# Decoder.net
KiCad netlist of a schematic drawn in EAGLE
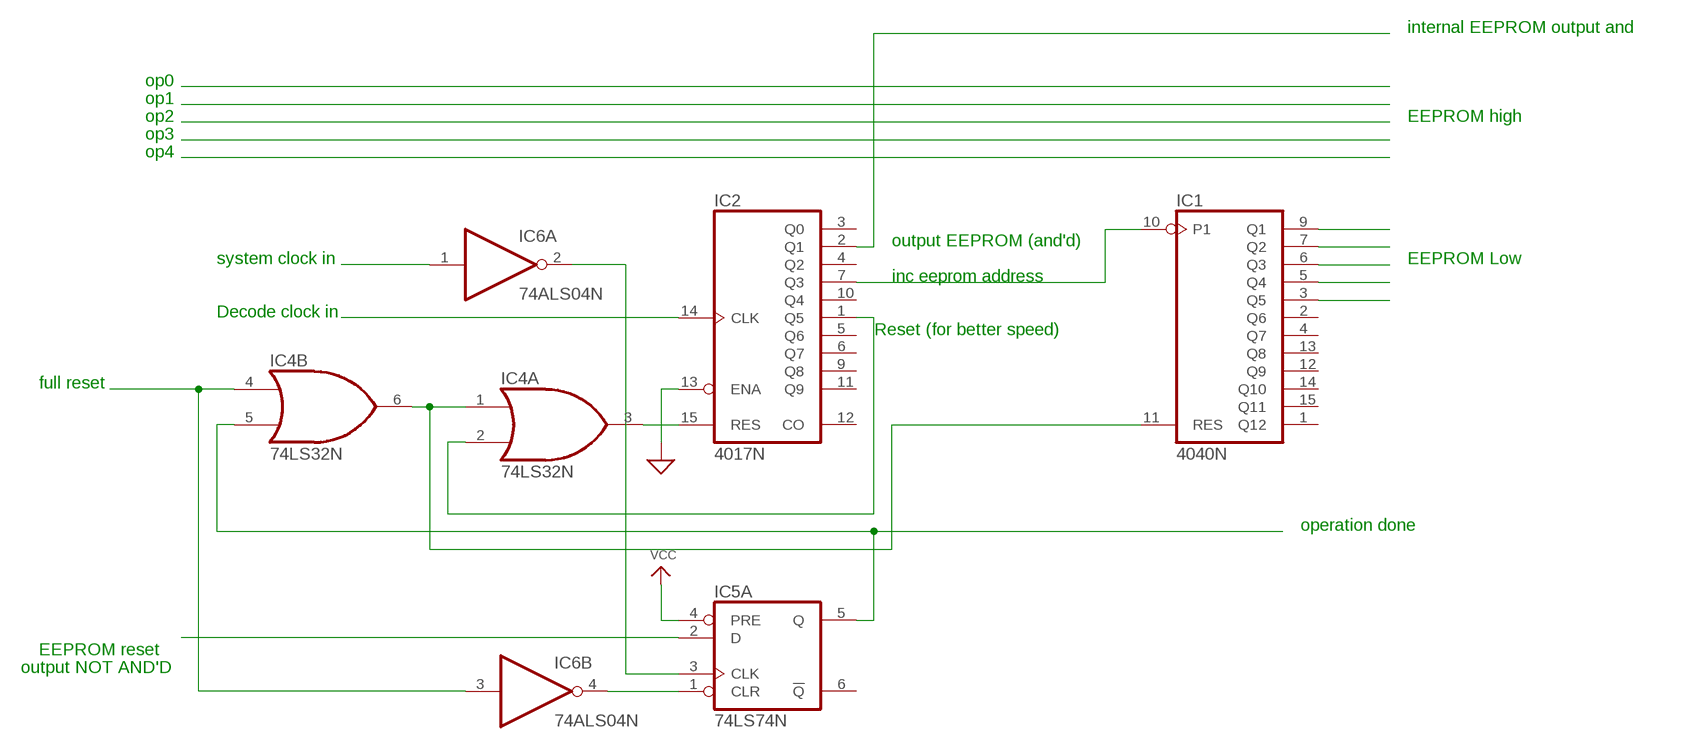
[diagram p0: schematic, sheet 1]

(export (version "E")
  (design (tool "Eeschema 10.0.6"))
  (components
    (comp (ref "IC1")
      (value "4040N")
      (footprint "eagle-import:DIL16")
      (libsource (lib "eagle-import") (part "4040N"))
    )
    (comp (ref "IC2")
      (value "4017N")
      (footprint "eagle-import:DIL16")
      (libsource (lib "eagle-import") (part "4017N"))
    )
    (comp (ref "IC4")
      (value "74LS32N")
      (footprint "eagle-import:DIL14")
      (libsource (lib "eagle-import") (part "7432NLS"))
    )
    (comp (ref "IC5")
      (value "74LS74N")
      (footprint "eagle-import:DIL14")
      (libsource (lib "eagle-import") (part "7474NLS"))
    )
    (comp (ref "IC6")
      (value "74ALS04N")
      (footprint "eagle-import:DIL14")
      (libsource (lib "eagle-import") (part "7404NALS"))
    )
  )
  (nets
    (net (code "1") (name "Net-(IC1A-P1)") (class "Default")
      (node (ref "IC1") (pin "10") (pinfunction "P1_10") (pintype "input"))
      (node (ref "IC2") (pin "7") (pinfunction "Q3_7") (pintype "output"))
    )
    (net (code "2") (name "Net-(IC1A-RES)") (class "Default")
      (node (ref "IC1") (pin "11") (pinfunction "RES_11") (pintype "input"))
      (node (ref "IC4") (pin "1") (pinfunction "I0_1") (pintype "input"))
      (node (ref "IC4") (pin "6") (pinfunction "O_6") (pintype "output"))
    )
    (net (code "3") (name "Net-(IC2A-Q5)") (class "Default")
      (node (ref "IC2") (pin "1") (pinfunction "Q5_1") (pintype "output"))
      (node (ref "IC4") (pin "2") (pinfunction "I1_2") (pintype "input"))
    )
    (net (code "4") (name "Net-(IC2A-RES)") (class "Default")
      (node (ref "IC2") (pin "15") (pinfunction "RES_15") (pintype "input"))
      (node (ref "IC4") (pin "3") (pinfunction "O_3") (pintype "output"))
    )
    (net (code "5") (name "Net-(IC4B-I0)") (class "Default")
      (node (ref "IC4") (pin "4") (pinfunction "I0_4") (pintype "input"))
      (node (ref "IC6") (pin "3") (pinfunction "I_3") (pintype "input"))
    )
    (net (code "6") (name "Net-(IC4B-I1)") (class "Default")
      (node (ref "IC4") (pin "5") (pinfunction "I1_5") (pintype "input"))
      (node (ref "IC5") (pin "5") (pinfunction "Q_5") (pintype "output"))
    )
    (net (code "7") (name "Net-(IC5A-CLK)") (class "Default")
      (node (ref "IC5") (pin "3") (pinfunction "CLK_3") (pintype "input"))
      (node (ref "IC6") (pin "2") (pinfunction "O_2") (pintype "output"))
    )
    (net (code "8") (name "Net-(IC5A-CLR)") (class "Default")
      (node (ref "IC5") (pin "1") (pinfunction "CLR_1") (pintype "input"))
      (node (ref "IC6") (pin "4") (pinfunction "O_4") (pintype "output"))
    )
    (net (code "9") (name "SUP") (class "Default")
      (node (ref "IC2") (pin "13") (pinfunction "ENA_13") (pintype "input"))
    )
    (net (code "10") (name "VCC") (class "Default")
      (node (ref "IC5") (pin "4") (pinfunction "PRE_4") (pintype "input"))
    )
    (net (code "11") (name "unconnected-(IC1A-Q1-Pad9)") (class "Default")
      (node (ref "IC1") (pin "9") (pinfunction "Q1_9") (pintype "output"))
    )
    (net (code "12") (name "unconnected-(IC1A-Q2-Pad7)") (class "Default")
      (node (ref "IC1") (pin "7") (pinfunction "Q2_7") (pintype "output"))
    )
    (net (code "13") (name "unconnected-(IC1A-Q3-Pad6)") (class "Default")
      (node (ref "IC1") (pin "6") (pinfunction "Q3_6") (pintype "output"))
    )
    (net (code "14") (name "unconnected-(IC1A-Q4-Pad5)") (class "Default")
      (node (ref "IC1") (pin "5") (pinfunction "Q4_5") (pintype "output"))
    )
    (net (code "15") (name "unconnected-(IC1A-Q5-Pad3)") (class "Default")
      (node (ref "IC1") (pin "3") (pinfunction "Q5_3") (pintype "output"))
    )
    (net (code "16") (name "unconnected-(IC1A-Q6-Pad2)") (class "Default")
      (node (ref "IC1") (pin "2") (pinfunction "Q6_2") (pintype "output"))
    )
    (net (code "17") (name "unconnected-(IC1A-Q7-Pad4)") (class "Default")
      (node (ref "IC1") (pin "4") (pinfunction "Q7_4") (pintype "output"))
    )
    (net (code "18") (name "unconnected-(IC1A-Q8-Pad13)") (class "Default")
      (node (ref "IC1") (pin "13") (pinfunction "Q8_13") (pintype "output"))
    )
    (net (code "19") (name "unconnected-(IC1A-Q9-Pad12)") (class "Default")
      (node (ref "IC1") (pin "12") (pinfunction "Q9_12") (pintype "output"))
    )
    (net (code "20") (name "unconnected-(IC1A-Q10-Pad14)") (class "Default")
      (node (ref "IC1") (pin "14") (pinfunction "Q10_14") (pintype "output"))
    )
    (net (code "21") (name "unconnected-(IC1A-Q11-Pad15)") (class "Default")
      (node (ref "IC1") (pin "15") (pinfunction "Q11_15") (pintype "output"))
    )
    (net (code "22") (name "unconnected-(IC1A-Q12-Pad1)") (class "Default")
      (node (ref "IC1") (pin "1") (pinfunction "Q12_1") (pintype "output"))
    )
    (net (code "23") (name "unconnected-(IC2A-CLK-Pad14)") (class "Default")
      (node (ref "IC2") (pin "14") (pinfunction "CLK_14") (pintype "input"))
    )
    (net (code "24") (name "unconnected-(IC2A-CO-Pad12)") (class "Default")
      (node (ref "IC2") (pin "12") (pinfunction "CO_12") (pintype "output"))
    )
    (net (code "25") (name "unconnected-(IC2A-Q0-Pad3)") (class "Default")
      (node (ref "IC2") (pin "3") (pinfunction "Q0_3") (pintype "output"))
    )
    (net (code "26") (name "unconnected-(IC2A-Q1-Pad2)") (class "Default")
      (node (ref "IC2") (pin "2") (pinfunction "Q1_2") (pintype "output"))
    )
    (net (code "27") (name "unconnected-(IC2A-Q2-Pad4)") (class "Default")
      (node (ref "IC2") (pin "4") (pinfunction "Q2_4") (pintype "output"))
    )
    (net (code "28") (name "unconnected-(IC2A-Q4-Pad10)") (class "Default")
      (node (ref "IC2") (pin "10") (pinfunction "Q4_10") (pintype "output"))
    )
    (net (code "29") (name "unconnected-(IC2A-Q6-Pad5)") (class "Default")
      (node (ref "IC2") (pin "5") (pinfunction "Q6_5") (pintype "output"))
    )
    (net (code "30") (name "unconnected-(IC2A-Q7-Pad6)") (class "Default")
      (node (ref "IC2") (pin "6") (pinfunction "Q7_6") (pintype "output"))
    )
    (net (code "31") (name "unconnected-(IC2A-Q8-Pad9)") (class "Default")
      (node (ref "IC2") (pin "9") (pinfunction "Q8_9") (pintype "output"))
    )
    (net (code "32") (name "unconnected-(IC2A-Q9-Pad11)") (class "Default")
      (node (ref "IC2") (pin "11") (pinfunction "Q9_11") (pintype "output"))
    )
    (net (code "33") (name "unconnected-(IC5A-D-Pad2)") (class "Default")
      (node (ref "IC5") (pin "2") (pinfunction "D_2") (pintype "input"))
    )
    (net (code "34") (name "unconnected-(IC5A-~{Q}-Pad6)") (class "Default")
      (node (ref "IC5") (pin "6") (pinfunction "~{Q}_6") (pintype "output"))
    )
    (net (code "35") (name "unconnected-(IC6A-I-Pad1)") (class "Default")
      (node (ref "IC6") (pin "1") (pinfunction "I_1") (pintype "input"))
    )
  )
)
